# NTC.net
KiCad netlist of a schematic drawn in Altium Designer
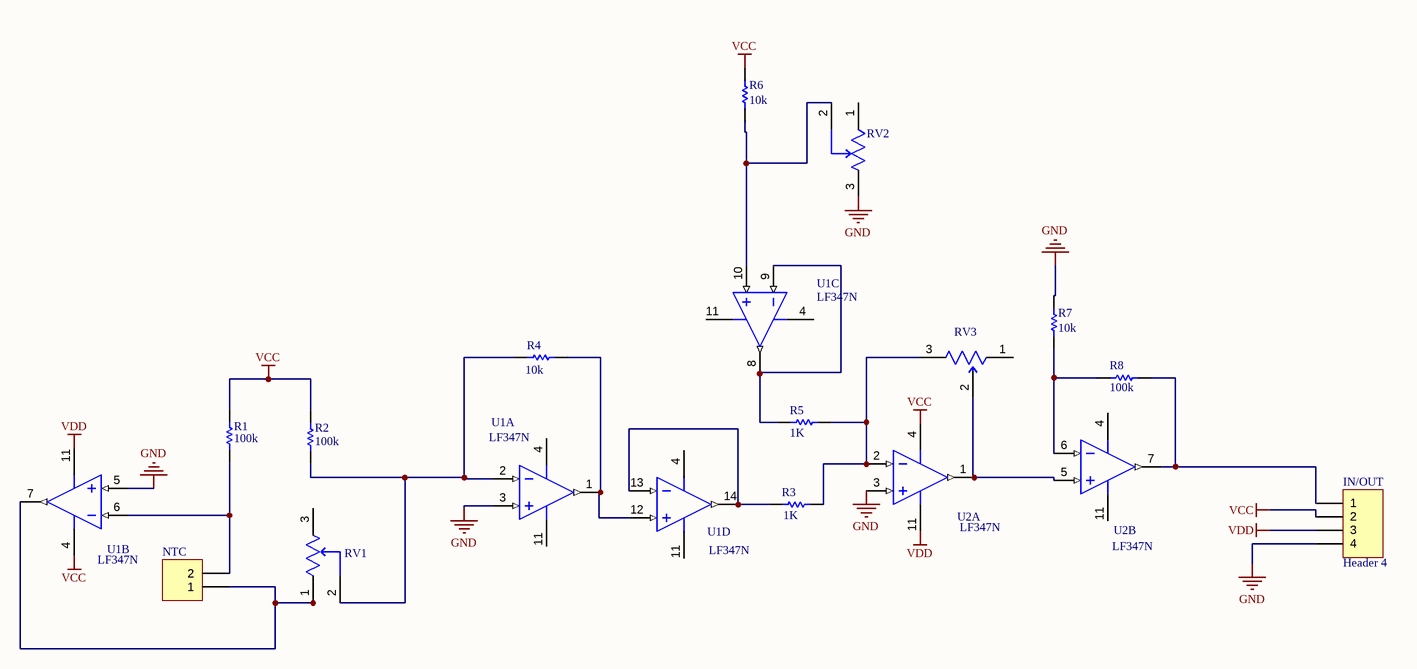
[diagram p0: NTC.SchDoc]

(export (version "E")
  (design (tool "Eeschema 10.0.6"))
  (components
    (comp (ref "IN/OUT")
      (value "Header 4")
      (footprint "HDR1X4")
      (description "Header, 4-Pin\r\n1 for out\r\n2 for Vcc\r\n3 for Vdd\r\n4 for GND")
      (fields (field (name "PUBLISHER") "Altium Limited"))
      (libsource (lib "Miscellaneous Connectors") (part "Header 4"))
    )
    (comp (ref "NTC")
      (value "Thermoresistor")
      (footprint "MHDR1X2")
      (description "Header, 2-Pin")
      (fields (field (name "PUBLISHER") "Altium Limited"))
      (libsource (lib "Miscellaneous Connectors") (part "MHDR1X2"))
    )
    (comp (ref "R1")
      (value "100k")
      (footprint "AXIAL-0.3")
      (description "Resistor")
      (fields (field (name "Comment") "Res1") (field (name "PUBLISHER") "Altium Limited"))
      (libsource (lib "Miscellaneous Devices") (part "Res1"))
    )
    (comp (ref "R2")
      (value "100k")
      (footprint "AXIAL-0.3")
      (description "Resistor")
      (fields (field (name "Comment") "Res1") (field (name "PUBLISHER") "Altium Limited"))
      (libsource (lib "Miscellaneous Devices") (part "Res1"))
    )
    (comp (ref "R3")
      (value "1K")
      (footprint "AXIAL-0.3")
      (description "Resistor")
      (fields (field (name "Comment") "Res1") (field (name "PUBLISHER") "Altium Limited"))
      (libsource (lib "Miscellaneous Devices") (part "Res1"))
    )
    (comp (ref "R4")
      (value "10k")
      (footprint "AXIAL-0.3")
      (description "Resistor")
      (fields (field (name "Comment") "Res1") (field (name "PUBLISHER") "Altium Limited"))
      (libsource (lib "Miscellaneous Devices") (part "Res1"))
    )
    (comp (ref "R5")
      (value "1K")
      (footprint "AXIAL-0.3")
      (description "Resistor")
      (fields (field (name "Comment") "Res1") (field (name "PUBLISHER") "Altium Limited"))
      (libsource (lib "Miscellaneous Devices") (part "Res1"))
    )
    (comp (ref "R6")
      (value "10k")
      (footprint "AXIAL-0.3")
      (description "Resistor")
      (fields (field (name "Comment") "Res1") (field (name "PUBLISHER") "Altium Limited"))
      (libsource (lib "Miscellaneous Devices") (part "Res1"))
    )
    (comp (ref "R7")
      (value "10k")
      (footprint "AXIAL-0.3")
      (description "Resistor")
      (fields (field (name "Comment") "Res1") (field (name "PUBLISHER") "Altium Limited"))
      (libsource (lib "Miscellaneous Devices") (part "Res1"))
    )
    (comp (ref "R8")
      (value "100k")
      (footprint "AXIAL-0.3")
      (description "Resistor")
      (fields (field (name "Comment") "Res1") (field (name "PUBLISHER") "Altium Limited"))
      (libsource (lib "Miscellaneous Devices") (part "Res1"))
    )
    (comp (ref "RV1")
      (value "3296W-1-504LF")
      (footprint "FP-3296W-MFG")
      (description "TRIMMER 500K OHM 0.5W PC PIN TOP")
      (fields
        (field (name "MANUFACTURER") "Bourns")
        (field (name "OCTOPART") "https://octopart.com/3296w-1-504lf-bourns-143884")
      )
      (libsource (lib "Altium Content Vault") (part "8d460c8a6f7ec10b1759d1b9c49aa93"))
    )
    (comp (ref "RV2")
      (value "3296W-1-504LF")
      (footprint "FP-3296W-MFG")
      (description "TRIMMER 500K OHM 0.5W PC PIN TOP")
      (fields
        (field (name "MANUFACTURER") "Bourns")
        (field (name "OCTOPART") "https://octopart.com/3296w-1-504lf-bourns-143884")
      )
      (libsource (lib "Altium Content Vault") (part "8d460c8a6f7ec10b1759d1b9c49aa93"))
    )
    (comp (ref "RV3")
      (value "3006P-1-103LF")
      (footprint "FP-3006P-MFG")
      (description "TRIMMER 10KOHM 0.75W PC PIN SIDE")
      (fields (field (name "TOLERANCE") "10%"))
      (libsource (lib "Altium Content Vault") (part "ad0de4570dda44d2fdef8f57041519a"))
    )
    (comp (ref "U1")
      (value "LF347N")
      (footprint "N0014A")
      (description "Wide Bandwidth Quad JFET Input Operational Amplifier, 14-pin MDIP")
      (fields (field (name "MANUFACTURER") "Texas Instruments"))
      (libsource (lib "Altium Content Vault") (part "AMP-OPA-LF147-14"))
    )
    (comp (ref "U2")
      (value "LF347N")
      (footprint "N0014A")
      (description "Wide Bandwidth Quad JFET Input Operational Amplifier, 14-pin MDIP")
      (fields (field (name "MANUFACTURER") "Texas Instruments"))
      (libsource (lib "Altium Content Vault") (part "AMP-OPA-LF147-14"))
    )
  )
  (nets
    (net (code "1") (name "GND") (class "Default")
      (node (ref "IN/OUT") (pin "4") (pinfunction "4_4") (pintype "passive"))
      (node (ref "R7") (pin "2") (pinfunction "2_2") (pintype "passive"))
      (node (ref "RV2") (pin "3") (pinfunction "CW_3") (pintype "passive"))
      (node (ref "U1") (pin "3") (pinfunction "IN1+_3") (pintype "input"))
      (node (ref "U1") (pin "5") (pinfunction "IN2+_5") (pintype "input"))
      (node (ref "U2") (pin "3") (pinfunction "IN1+_3") (pintype "input"))
    )
    (net (code "2") (name "Net-(RV1-CCW)") (class "Default")
      (node (ref "NTC") (pin "1") (pinfunction "1_1") (pintype "passive"))
      (node (ref "RV1") (pin "1") (pinfunction "CCW_1") (pintype "passive"))
      (node (ref "U1") (pin "7") (pinfunction "OUT2_7") (pintype "output"))
    )
    (net (code "3") (name "Net-(RV1-WIPER)") (class "Default")
      (node (ref "R2") (pin "1") (pinfunction "1_1") (pintype "passive"))
      (node (ref "R4") (pin "1") (pinfunction "1_1") (pintype "passive"))
      (node (ref "RV1") (pin "2") (pinfunction "WIPER_2") (pintype "passive"))
      (node (ref "U1") (pin "2") (pinfunction "IN1-_2") (pintype "input"))
    )
    (net (code "4") (name "Net-(RV2-WIPER)") (class "Default")
      (node (ref "R6") (pin "1") (pinfunction "1_1") (pintype "passive"))
      (node (ref "RV2") (pin "2") (pinfunction "WIPER_2") (pintype "passive"))
      (node (ref "U1") (pin "10") (pinfunction "IN3+_10") (pintype "input"))
    )
    (net (code "5") (name "Net-(RV3-CW)") (class "Default")
      (node (ref "R3") (pin "2") (pinfunction "2_2") (pintype "passive"))
      (node (ref "R5") (pin "2") (pinfunction "2_2") (pintype "passive"))
      (node (ref "RV3") (pin "3") (pinfunction "CW_3") (pintype "passive"))
      (node (ref "U2") (pin "2") (pinfunction "IN1-_2") (pintype "input"))
    )
    (net (code "6") (name "Net-(RV3-WIPER)") (class "Default")
      (node (ref "RV3") (pin "2") (pinfunction "WIPER_2") (pintype "passive"))
      (node (ref "U2") (pin "1") (pinfunction "OUT1_1") (pintype "output"))
      (node (ref "U2") (pin "5") (pinfunction "IN2+_5") (pintype "input"))
    )
    (net (code "7") (name "Net-(U1A-OUT1)") (class "Default")
      (node (ref "R4") (pin "2") (pinfunction "2_2") (pintype "passive"))
      (node (ref "U1") (pin "1") (pinfunction "OUT1_1") (pintype "output"))
      (node (ref "U1") (pin "12") (pinfunction "IN4+_12") (pintype "input"))
    )
    (net (code "8") (name "Net-(U1B-IN2-)") (class "Default")
      (node (ref "NTC") (pin "2") (pinfunction "2_2") (pintype "passive"))
      (node (ref "R1") (pin "1") (pinfunction "1_1") (pintype "passive"))
      (node (ref "U1") (pin "6") (pinfunction "IN2-_6") (pintype "input"))
    )
    (net (code "9") (name "Net-(U1C-IN3-)") (class "Default")
      (node (ref "R5") (pin "1") (pinfunction "1_1") (pintype "passive"))
      (node (ref "U1") (pin "8") (pinfunction "OUT3_8") (pintype "output"))
      (node (ref "U1") (pin "9") (pinfunction "IN3-_9") (pintype "input"))
    )
    (net (code "10") (name "Net-(U1D-IN4-)") (class "Default")
      (node (ref "R3") (pin "1") (pinfunction "1_1") (pintype "passive"))
      (node (ref "U1") (pin "13") (pinfunction "IN4-_13") (pintype "input"))
      (node (ref "U1") (pin "14") (pinfunction "OUT4_14") (pintype "output"))
    )
    (net (code "11") (name "Net-(U2B-IN2-)") (class "Default")
      (node (ref "R7") (pin "1") (pinfunction "1_1") (pintype "passive"))
      (node (ref "R8") (pin "1") (pinfunction "1_1") (pintype "passive"))
      (node (ref "U2") (pin "6") (pinfunction "IN2-_6") (pintype "input"))
    )
    (net (code "12") (name "Net-(U2B-OUT2)") (class "Default")
      (node (ref "IN/OUT") (pin "1") (pinfunction "1_1") (pintype "passive"))
      (node (ref "R8") (pin "2") (pinfunction "2_2") (pintype "passive"))
      (node (ref "U2") (pin "7") (pinfunction "OUT2_7") (pintype "output"))
    )
    (net (code "13") (name "VCC") (class "Default")
      (node (ref "IN/OUT") (pin "2") (pinfunction "2_2") (pintype "passive"))
      (node (ref "R1") (pin "2") (pinfunction "2_2") (pintype "passive"))
      (node (ref "R2") (pin "2") (pinfunction "2_2") (pintype "passive"))
      (node (ref "R6") (pin "2") (pinfunction "2_2") (pintype "passive"))
      (node (ref "U1") (pin "4") (pinfunction "V+_4") (pintype "power_in"))
      (node (ref "U2") (pin "4") (pinfunction "V+_4") (pintype "power_in"))
    )
    (net (code "14") (name "VDD") (class "Default")
      (node (ref "IN/OUT") (pin "3") (pinfunction "3_3") (pintype "passive"))
      (node (ref "U1") (pin "11") (pinfunction "V-_11") (pintype "power_in"))
      (node (ref "U2") (pin "11") (pinfunction "V-_11") (pintype "power_in"))
    )
    (net (code "15") (name "unconnected-(RV1-CW-Pad3)") (class "Default")
      (node (ref "RV1") (pin "3") (pinfunction "CW_3") (pintype "passive"))
    )
    (net (code "16") (name "unconnected-(RV2-CCW-Pad1)") (class "Default")
      (node (ref "RV2") (pin "1") (pinfunction "CCW_1") (pintype "passive"))
    )
    (net (code "17") (name "unconnected-(RV3-CCW-Pad1)") (class "Default")
      (node (ref "RV3") (pin "1") (pinfunction "CCW_1") (pintype "passive"))
    )
    (net (code "18") (name "unconnected-(U1A-V+-Pad4)") (class "Default")
      (node (ref "U1") (pin "4") (pinfunction "V+_4") (pintype "power_in"))
    )
    (net (code "19") (name "unconnected-(U1A-V--Pad11)") (class "Default")
      (node (ref "U1") (pin "11") (pinfunction "V-_11") (pintype "power_in"))
    )
    (net (code "20") (name "unconnected-(U1C-V+-Pad4)") (class "Default")
      (node (ref "U1") (pin "4") (pinfunction "V+_4") (pintype "power_in"))
    )
    (net (code "21") (name "unconnected-(U1C-V--Pad11)") (class "Default")
      (node (ref "U1") (pin "11") (pinfunction "V-_11") (pintype "power_in"))
    )
    (net (code "22") (name "unconnected-(U1D-V+-Pad4)") (class "Default")
      (node (ref "U1") (pin "4") (pinfunction "V+_4") (pintype "power_in"))
    )
    (net (code "23") (name "unconnected-(U1D-V--Pad11)") (class "Default")
      (node (ref "U1") (pin "11") (pinfunction "V-_11") (pintype "power_in"))
    )
    (net (code "24") (name "unconnected-(U2B-V+-Pad4)") (class "Default")
      (node (ref "U2") (pin "4") (pinfunction "V+_4") (pintype "power_in"))
    )
    (net (code "25") (name "unconnected-(U2B-V--Pad11)") (class "Default")
      (node (ref "U2") (pin "11") (pinfunction "V-_11") (pintype "power_in"))
    )
  )
)
